# gba-zero.net
KiCad netlist of a schematic drawn in EAGLE
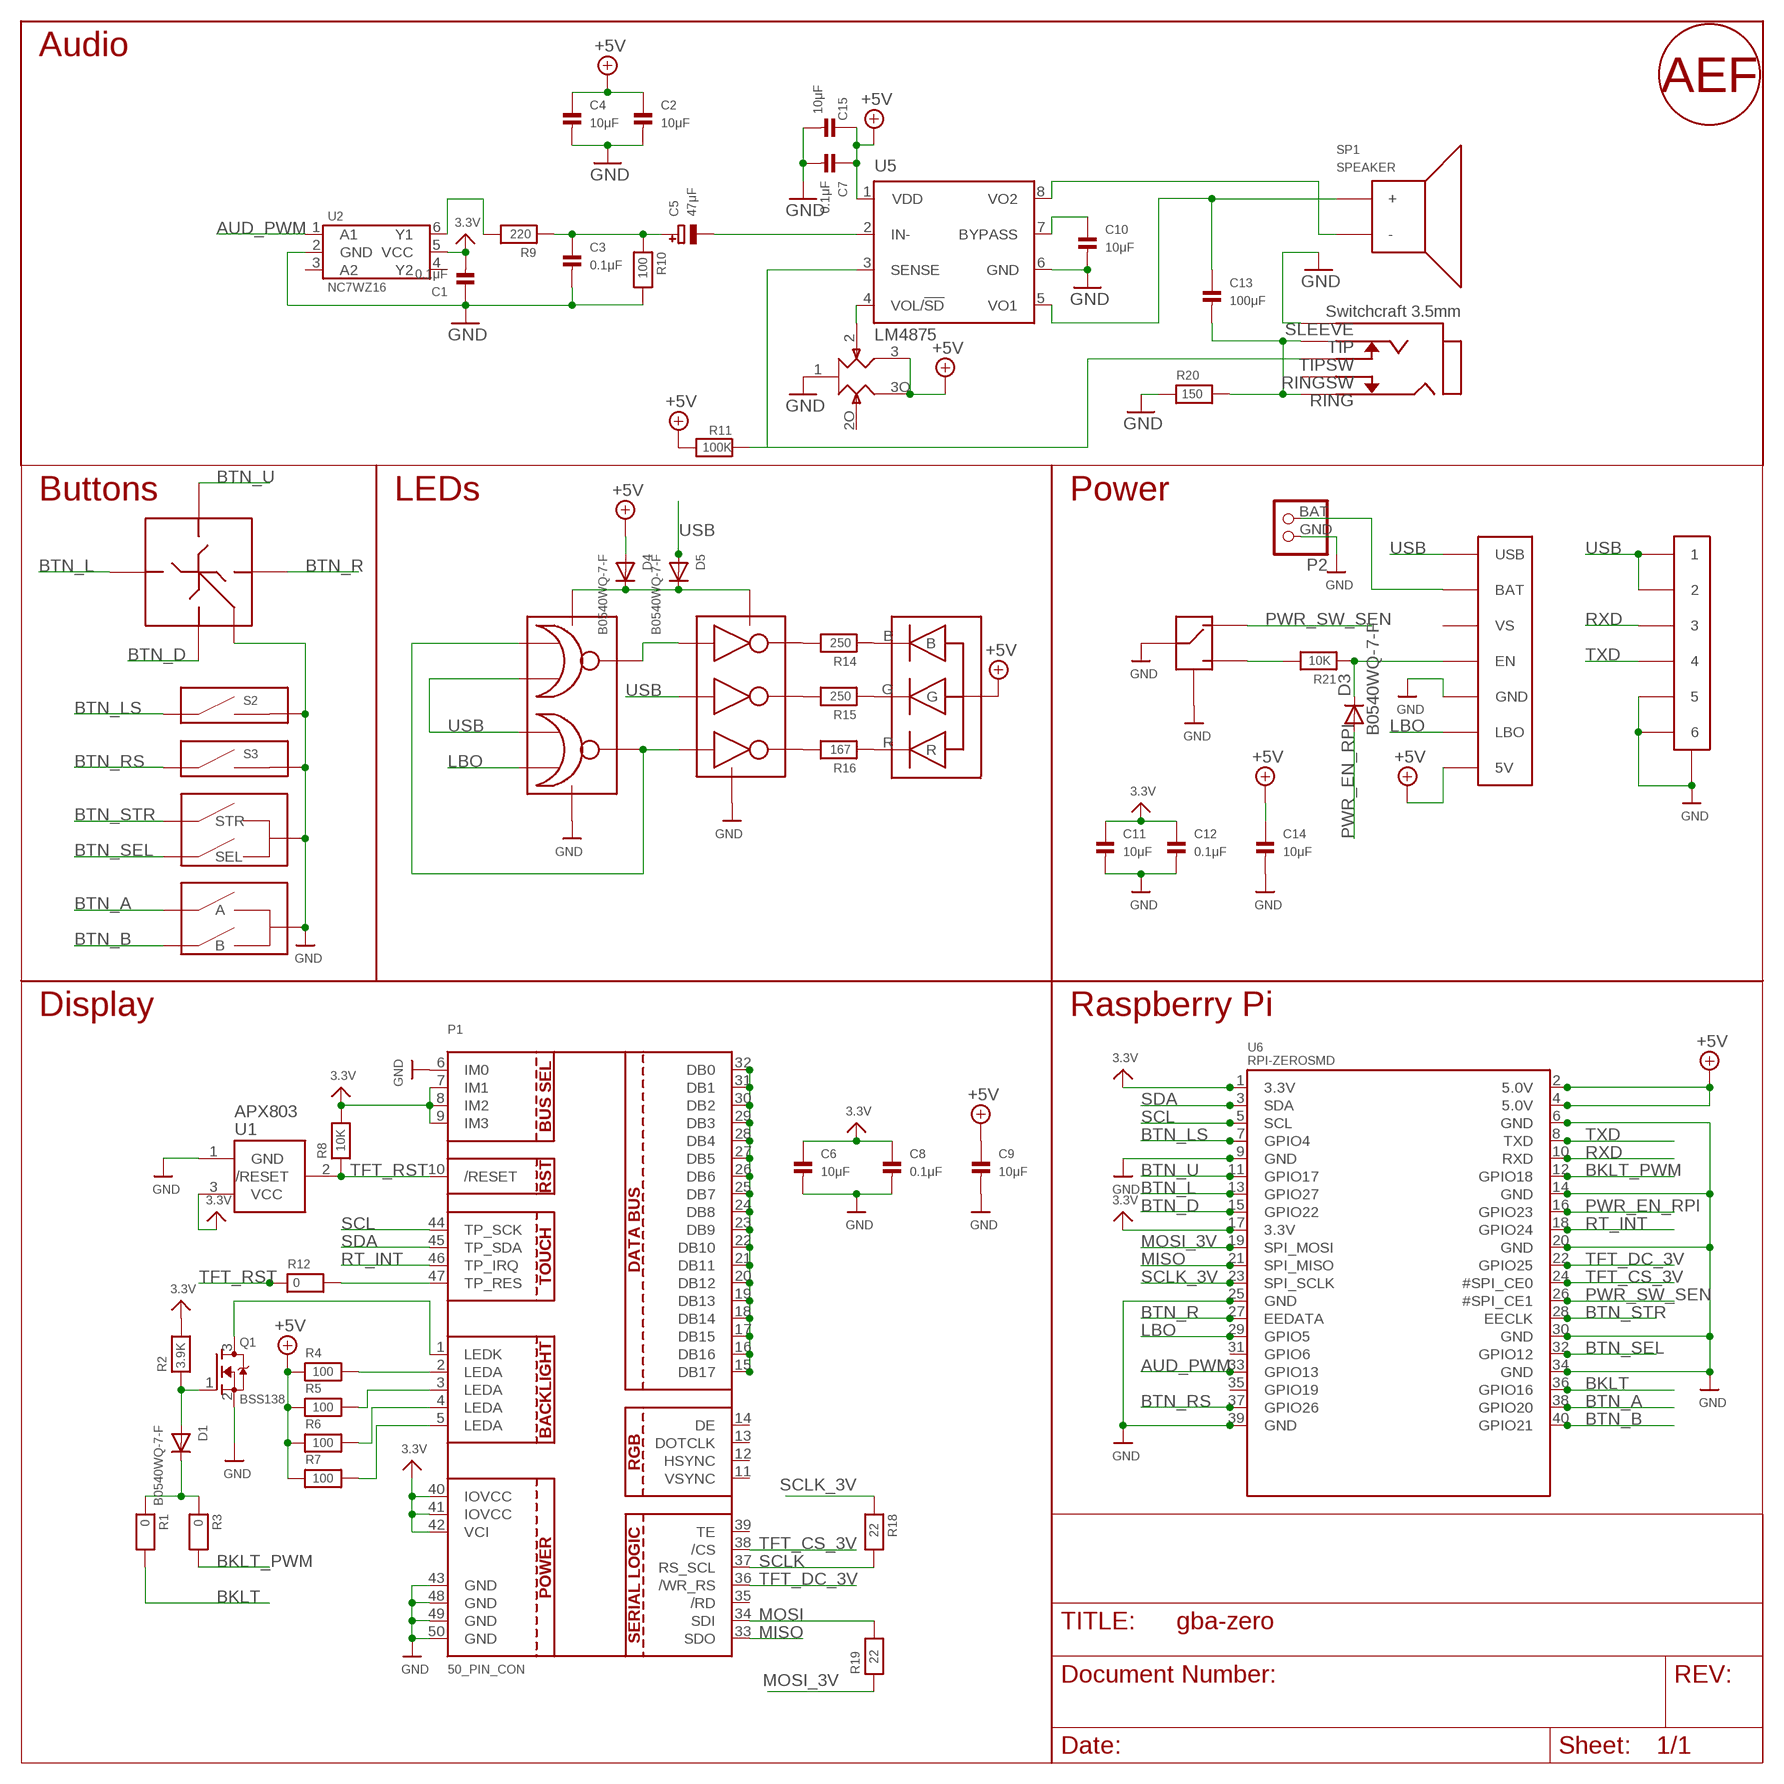
[diagram p0: schematic, sheet 1]

(export (version "E")
  (design (tool "Eeschema 10.0.6"))
  (components
    (comp (ref "C1")
      (value "0.1μF")
      (footprint "eagle-import:0603")
      (libsource (lib "eagle-import") (part "CAP_CERAMIC0603"))
    )
    (comp (ref "C2")
      (value "10μF")
      (footprint "eagle-import:0603")
      (libsource (lib "eagle-import") (part "CAP_CERAMIC0603"))
    )
    (comp (ref "C3")
      (value "0.1μF")
      (footprint "eagle-import:0603")
      (libsource (lib "eagle-import") (part "CAP_CERAMIC0603"))
    )
    (comp (ref "C4")
      (value "10μF")
      (footprint "eagle-import:0603")
      (libsource (lib "eagle-import") (part "CAP_CERAMIC0603"))
    )
    (comp (ref "C5")
      (value "47μF")
      (footprint "eagle-import:EIA6032-28_C-R")
      (libsource (lib "eagle-import") (part "CAP_TANTALUMC/6032_REFLOW"))
    )
    (comp (ref "C6")
      (value "10μF")
      (footprint "eagle-import:0603")
      (libsource (lib "eagle-import") (part "CAP_CERAMIC0603"))
    )
    (comp (ref "C7")
      (value "0.1μF")
      (footprint "eagle-import:0603")
      (libsource (lib "eagle-import") (part "CAP_CERAMIC0603"))
    )
    (comp (ref "C8")
      (value "0.1μF")
      (footprint "eagle-import:0603")
      (libsource (lib "eagle-import") (part "CAP_CERAMIC0603"))
    )
    (comp (ref "C9")
      (value "10μF")
      (footprint "eagle-import:0603")
      (libsource (lib "eagle-import") (part "CAP_CERAMIC0603"))
    )
    (comp (ref "C10")
      (value "10μF")
      (footprint "eagle-import:0603")
      (libsource (lib "eagle-import") (part "CAP_CERAMIC0603"))
    )
    (comp (ref "C11")
      (value "10μF")
      (footprint "eagle-import:0603")
      (libsource (lib "eagle-import") (part "CAP_CERAMIC0603"))
    )
    (comp (ref "C12")
      (value "0.1μF")
      (footprint "eagle-import:0603")
      (libsource (lib "eagle-import") (part "CAP_CERAMIC0603"))
    )
    (comp (ref "C13")
      (value "100μF")
      (footprint "eagle-import:1206")
      (libsource (lib "eagle-import") (part "CAP_CERAMIC1206"))
    )
    (comp (ref "C14")
      (value "10μF")
      (footprint "eagle-import:0603")
      (libsource (lib "eagle-import") (part "CAP_CERAMIC0603"))
    )
    (comp (ref "C15")
      (value "10μF")
      (footprint "eagle-import:0603")
      (libsource (lib "eagle-import") (part "CAP_CERAMIC0603"))
    )
    (comp (ref "D1")
      (value "B0540WQ-7-F")
      (footprint "eagle-import:SOD-123")
      (libsource (lib "eagle-import") (part "DIODESOD-123"))
    )
    (comp (ref "D2")
      (value "LTST-C19HE1WT")
      (footprint "eagle-import:WL-SBCW-0606")
      (libsource (lib "eagle-import") (part "LTST-C19HE1WT"))
    )
    (comp (ref "D3")
      (value "B0540WQ-7-F")
      (footprint "eagle-import:SOD-123")
      (libsource (lib "eagle-import") (part "DIODESOD-123"))
    )
    (comp (ref "D4")
      (value "B0540WQ-7-F")
      (footprint "eagle-import:SOD-123")
      (libsource (lib "eagle-import") (part "DIODESOD-123"))
    )
    (comp (ref "D5")
      (value "B0540WQ-7-F")
      (footprint "eagle-import:SOD-123")
      (libsource (lib "eagle-import") (part "DIODESOD-123"))
    )
    (comp (ref "J1")
      (value "SWTCHCRFT_3.5JACK5-JACK-SMD")
      (footprint "eagle-import:4-JACK-SMD")
      (libsource (lib "eagle-import") (part "SWTCHCRFT_3.5JACK5-JACK-SMD"))
    )
    (comp (ref "P1")
      (value "50_PIN_CON")
      (footprint "eagle-import:FPC-50-CON")
      (libsource (lib "eagle-import") (part "DISP_LCD_CTP28"))
    )
    (comp (ref "P2")
      (value "JST_2PIN")
      (footprint "eagle-import:JSTPH2")
      (libsource (lib "eagle-import") (part "JST_2PIN"))
    )
    (comp (ref "P3")
      (value "LINK_CONNECTOR")
      (footprint "eagle-import:LINK_CONNECTOR")
      (libsource (lib "eagle-import") (part "LINK_CONNECTOR"))
    )
    (comp (ref "Q1")
      (value "BSS138")
      (footprint "eagle-import:SOT23-WIDE")
      (libsource (lib "eagle-import") (part "MOSFET-NWIDE"))
    )
    (comp (ref "R1")
      (value "0")
      (footprint "eagle-import:0603")
      (libsource (lib "eagle-import") (part "RESISTOR0603"))
    )
    (comp (ref "R2")
      (value "3.9K")
      (footprint "eagle-import:0603")
      (libsource (lib "eagle-import") (part "RESISTOR0603"))
    )
    (comp (ref "R3")
      (value "0")
      (footprint "eagle-import:0603")
      (libsource (lib "eagle-import") (part "RESISTOR0603"))
    )
    (comp (ref "R4")
      (value "100")
      (footprint "eagle-import:0603")
      (libsource (lib "eagle-import") (part "RESISTOR0603"))
    )
    (comp (ref "R5")
      (value "100")
      (footprint "eagle-import:0603")
      (libsource (lib "eagle-import") (part "RESISTOR0603"))
    )
    (comp (ref "R6")
      (value "100")
      (footprint "eagle-import:0603")
      (libsource (lib "eagle-import") (part "RESISTOR0603"))
    )
    (comp (ref "R7")
      (value "100")
      (footprint "eagle-import:0603")
      (libsource (lib "eagle-import") (part "RESISTOR0603"))
    )
    (comp (ref "R8")
      (value "10K")
      (footprint "eagle-import:0603")
      (libsource (lib "eagle-import") (part "RESISTOR0603"))
    )
    (comp (ref "R9")
      (value "220")
      (footprint "eagle-import:0603")
      (libsource (lib "eagle-import") (part "RESISTOR0603"))
    )
    (comp (ref "R10")
      (value "100")
      (footprint "eagle-import:0603")
      (libsource (lib "eagle-import") (part "RESISTOR0603"))
    )
    (comp (ref "R11")
      (value "100K")
      (footprint "eagle-import:0603")
      (libsource (lib "eagle-import") (part "RESISTOR0603"))
    )
    (comp (ref "R12")
      (value "0")
      (footprint "eagle-import:0603")
      (libsource (lib "eagle-import") (part "RESISTOR0603"))
    )
    (comp (ref "R14")
      (value "250")
      (footprint "eagle-import:0603")
      (libsource (lib "eagle-import") (part "RESISTOR0603"))
    )
    (comp (ref "R15")
      (value "250")
      (footprint "eagle-import:0603")
      (libsource (lib "eagle-import") (part "RESISTOR0603"))
    )
    (comp (ref "R16")
      (value "167")
      (footprint "eagle-import:0603")
      (libsource (lib "eagle-import") (part "RESISTOR0603"))
    )
    (comp (ref "R17")
      (value "10K")
      (footprint "eagle-import:RK10J12E0A0A")
      (libsource (lib "eagle-import") (part "RK10J12E0A0A"))
    )
    (comp (ref "R18")
      (value "22")
      (footprint "eagle-import:0603")
      (libsource (lib "eagle-import") (part "RESISTOR0603"))
    )
    (comp (ref "R19")
      (value "22")
      (footprint "eagle-import:0603")
      (libsource (lib "eagle-import") (part "RESISTOR0603"))
    )
    (comp (ref "R20")
      (value "150")
      (footprint "eagle-import:0603")
      (libsource (lib "eagle-import") (part "RESISTOR0603"))
    )
    (comp (ref "R21")
      (value "10K")
      (footprint "eagle-import:0603")
      (libsource (lib "eagle-import") (part "RESISTOR0603"))
    )
    (comp (ref "S1")
      (value "D-PAD")
      (footprint "eagle-import:D-PAD")
      (libsource (lib "eagle-import") (part "D-PAD"))
    )
    (comp (ref "S2")
      (value "SHOULDER_BUTTON")
      (footprint "eagle-import:SHOULDER_BUTTON")
      (libsource (lib "eagle-import") (part "SHOULDER_BUTTON"))
    )
    (comp (ref "S3")
      (value "SHOULDER_BUTTON")
      (footprint "eagle-import:SHOULDER_BUTTON")
      (libsource (lib "eagle-import") (part "SHOULDER_BUTTON"))
    )
    (comp (ref "S4")
      (value "START_SELECT_BUTTON")
      (footprint "eagle-import:START_SELECT_BUTTON")
      (libsource (lib "eagle-import") (part "START_SELECT_BUTTON"))
    )
    (comp (ref "S5")
      (value "AB_BUTTON")
      (footprint "eagle-import:AB_BUTTON")
      (libsource (lib "eagle-import") (part "AB_BUTTON"))
    )
    (comp (ref "S6")
      (value "PWR_SWITCH")
      (footprint "eagle-import:PWR-SWITCH")
      (libsource (lib "eagle-import") (part "PWR_SWITCH"))
    )
    (comp (ref "SP1")
      (value "SPEAKER")
      (footprint "eagle-import:SPEAKER")
      (libsource (lib "eagle-import") (part "SPEAKER"))
    )
    (comp (ref "U$1")
      (value "SIGNATURE")
      (footprint "eagle-import:SIGNATURE")
      (libsource (lib "eagle-import") (part "SIGNATURE"))
    )
    (comp (ref "U1")
      (value "APX803")
      (footprint "eagle-import:SOT23")
      (libsource (lib "eagle-import") (part "AXP083-SAG"))
    )
    (comp (ref "U2")
      (value "NC7WZ16")
      (footprint "eagle-import:SC-70-6")
      (libsource (lib "eagle-import") (part "NC7WZ16"))
    )
    (comp (ref "U3")
      (value "74LVC2G02")
      (footprint "eagle-import:TSSOP-8")
      (libsource (lib "eagle-import") (part "74LVC2G02"))
    )
    (comp (ref "U4")
      (value "74LVC3G04")
      (footprint "eagle-import:TSSOP-8")
      (libsource (lib "eagle-import") (part "74LVC3G04"))
    )
    (comp (ref "U5")
      (value "LM4875")
      (footprint "eagle-import:SO-8")
      (libsource (lib "eagle-import") (part "LM4875"))
    )
    (comp (ref "U6")
      (value "RPI-ZEROSMD")
      (footprint "eagle-import:RPI-SMD")
      (libsource (lib "eagle-import") (part "RPI-ZEROSMD"))
    )
    (comp (ref "U7")
      (value "POWERBOOST-1000C")
      (footprint "eagle-import:POWERBOOST-1000C")
      (libsource (lib "eagle-import") (part "POWERBOOST-1000C"))
    )
  )
  (nets
    (net (code "1") (name "+5V") (class "Default")
      (node (ref "C14") (pin "1") (pinfunction "P$1_1") (pintype "passive"))
      (node (ref "C15") (pin "1") (pinfunction "P$1_1") (pintype "passive"))
      (node (ref "C2") (pin "1") (pinfunction "P$1_1") (pintype "passive"))
      (node (ref "C4") (pin "1") (pinfunction "P$1_1") (pintype "passive"))
      (node (ref "C7") (pin "1") (pinfunction "P$1_1") (pintype "passive"))
      (node (ref "C9") (pin "1") (pinfunction "P$1_1") (pintype "passive"))
      (node (ref "D2") (pin "VCC") (pinfunction "VCC_VCC") (pintype "bidirectional"))
      (node (ref "D4") (pin "A") (pinfunction "A_A") (pintype "passive"))
      (node (ref "R11") (pin "2") (pinfunction "2_2") (pintype "passive"))
      (node (ref "R17") (pin "3") (pinfunction "3_3") (pintype "bidirectional"))
      (node (ref "R17") (pin "3O") (pinfunction "3O_3O") (pintype "bidirectional"))
      (node (ref "R4") (pin "1") (pinfunction "1_1") (pintype "passive"))
      (node (ref "R5") (pin "1") (pinfunction "1_1") (pintype "passive"))
      (node (ref "R6") (pin "1") (pinfunction "1_1") (pintype "passive"))
      (node (ref "R7") (pin "1") (pinfunction "1_1") (pintype "passive"))
      (node (ref "U5") (pin "1") (pinfunction "VDD_1") (pintype "power_in"))
      (node (ref "U6") (pin "2") (pinfunction "5.0V_2") (pintype "bidirectional"))
      (node (ref "U6") (pin "4") (pinfunction "5.0V_4") (pintype "bidirectional"))
      (node (ref "U7") (pin "5V") (pinfunction "5V_5V") (pintype "bidirectional"))
    )
    (net (code "2") (name "/AUD_PWM") (class "Default")
      (node (ref "U2") (pin "1") (pinfunction "A1_1") (pintype "bidirectional"))
      (node (ref "U6") (pin "33") (pinfunction "GPIO13_33") (pintype "bidirectional"))
    )
    (net (code "3") (name "/BKLT") (class "Default")
      (node (ref "R1") (pin "2") (pinfunction "2_2") (pintype "passive"))
      (node (ref "U6") (pin "36") (pinfunction "GPIO16_36") (pintype "bidirectional"))
    )
    (net (code "4") (name "/BKLT_PWM") (class "Default")
      (node (ref "R3") (pin "2") (pinfunction "2_2") (pintype "passive"))
      (node (ref "U6") (pin "12") (pinfunction "GPIO18_12") (pintype "bidirectional"))
    )
    (net (code "5") (name "/BTN_A") (class "Default")
      (node (ref "S5") (pin "A@1") (pinfunction "A_A@1") (pintype "bidirectional"))
      (node (ref "S5") (pin "A@2") (pinfunction "A_A@2") (pintype "bidirectional"))
      (node (ref "U6") (pin "38") (pinfunction "GPIO20_38") (pintype "bidirectional"))
    )
    (net (code "6") (name "/BTN_B") (class "Default")
      (node (ref "S5") (pin "B@1") (pinfunction "B_B@1") (pintype "bidirectional"))
      (node (ref "S5") (pin "B@2") (pinfunction "B_B@2") (pintype "bidirectional"))
      (node (ref "U6") (pin "40") (pinfunction "GPIO21_40") (pintype "bidirectional"))
    )
    (net (code "7") (name "/BTN_D") (class "Default")
      (node (ref "S1") (pin "DOWN") (pinfunction "DOWN_DOWN") (pintype "bidirectional"))
      (node (ref "U6") (pin "15") (pinfunction "GPIO22_15") (pintype "bidirectional"))
    )
    (net (code "8") (name "/BTN_L") (class "Default")
      (node (ref "S1") (pin "LEFT") (pinfunction "LEFT_LEFT") (pintype "bidirectional"))
      (node (ref "U6") (pin "13") (pinfunction "GPIO27_13") (pintype "bidirectional"))
    )
    (net (code "9") (name "/BTN_LS") (class "Default")
      (node (ref "S2") (pin "SW") (pinfunction "1_SW") (pintype "bidirectional"))
      (node (ref "U6") (pin "7") (pinfunction "GPIO4_7") (pintype "bidirectional"))
    )
    (net (code "10") (name "/BTN_R") (class "Default")
      (node (ref "S1") (pin "RIGHT") (pinfunction "RIGHT_RIGHT") (pintype "bidirectional"))
      (node (ref "U6") (pin "27") (pinfunction "EEDATA_27") (pintype "bidirectional"))
    )
    (net (code "11") (name "/BTN_RS") (class "Default")
      (node (ref "S3") (pin "SW") (pinfunction "1_SW") (pintype "bidirectional"))
      (node (ref "U6") (pin "37") (pinfunction "GPIO26_37") (pintype "bidirectional"))
    )
    (net (code "12") (name "/BTN_SEL") (class "Default")
      (node (ref "S4") (pin "SEL") (pinfunction "SEL_SEL") (pintype "bidirectional"))
      (node (ref "U6") (pin "32") (pinfunction "GPIO12_32") (pintype "bidirectional"))
    )
    (net (code "13") (name "/BTN_STR") (class "Default")
      (node (ref "S4") (pin "STR") (pinfunction "STR_STR") (pintype "bidirectional"))
      (node (ref "U6") (pin "28") (pinfunction "EECLK_28") (pintype "bidirectional"))
    )
    (net (code "14") (name "/BTN_U") (class "Default")
      (node (ref "S1") (pin "UP") (pinfunction "UP_UP") (pintype "bidirectional"))
      (node (ref "U6") (pin "11") (pinfunction "GPIO17_11") (pintype "bidirectional"))
    )
    (net (code "15") (name "/LBO") (class "Default")
      (node (ref "U3") (pin "6") (pinfunction "2B_6") (pintype "bidirectional"))
      (node (ref "U6") (pin "29") (pinfunction "GPIO5_29") (pintype "bidirectional"))
      (node (ref "U7") (pin "LBO") (pinfunction "LBO_LBO") (pintype "bidirectional"))
    )
    (net (code "16") (name "/MISO") (class "Default")
      (node (ref "P1") (pin "33") (pinfunction "SDO_33") (pintype "bidirectional"))
      (node (ref "U6") (pin "21") (pinfunction "SPI_MISO_21") (pintype "bidirectional"))
    )
    (net (code "17") (name "/MOSI") (class "Default")
      (node (ref "P1") (pin "34") (pinfunction "SDI_34") (pintype "bidirectional"))
      (node (ref "R19") (pin "2") (pinfunction "2_2") (pintype "passive"))
    )
    (net (code "18") (name "/MOSI_3V") (class "Default")
      (node (ref "R19") (pin "1") (pinfunction "1_1") (pintype "passive"))
      (node (ref "U6") (pin "19") (pinfunction "SPI_MOSI_19") (pintype "bidirectional"))
    )
    (net (code "19") (name "/PWR_EN_RPI") (class "Default")
      (node (ref "D3") (pin "A") (pinfunction "A_A") (pintype "passive"))
      (node (ref "U6") (pin "16") (pinfunction "GPIO23_16") (pintype "bidirectional"))
    )
    (net (code "20") (name "/PWR_SW_SEN") (class "Default")
      (node (ref "S6") (pin "L") (pinfunction "L_L") (pintype "bidirectional"))
      (node (ref "U6") (pin "26") (pinfunction "#SPI_CE1_26") (pintype "bidirectional"))
    )
    (net (code "21") (name "/RT_INT") (class "Default")
      (node (ref "P1") (pin "46") (pinfunction "TP_IRQ_46") (pintype "bidirectional"))
      (node (ref "U6") (pin "18") (pinfunction "GPIO24_18") (pintype "bidirectional"))
    )
    (net (code "22") (name "/RXD") (class "Default")
      (node (ref "P3") (pin "3") (pinfunction "3_3") (pintype "bidirectional"))
      (node (ref "U6") (pin "10") (pinfunction "RXD_10") (pintype "bidirectional"))
    )
    (net (code "23") (name "/SCL") (class "Default")
      (node (ref "P1") (pin "44") (pinfunction "TP_SCK_44") (pintype "bidirectional"))
      (node (ref "U6") (pin "5") (pinfunction "SCL_5") (pintype "bidirectional"))
    )
    (net (code "24") (name "/SCLK") (class "Default")
      (node (ref "P1") (pin "37") (pinfunction "RS_SCL_37") (pintype "bidirectional"))
      (node (ref "R18") (pin "2") (pinfunction "2_2") (pintype "passive"))
    )
    (net (code "25") (name "/SCLK_3V") (class "Default")
      (node (ref "R18") (pin "1") (pinfunction "1_1") (pintype "passive"))
      (node (ref "U6") (pin "23") (pinfunction "SPI_SCLK_23") (pintype "bidirectional"))
    )
    (net (code "26") (name "/SDA") (class "Default")
      (node (ref "P1") (pin "45") (pinfunction "TP_SDA_45") (pintype "bidirectional"))
      (node (ref "U6") (pin "3") (pinfunction "SDA_3") (pintype "bidirectional"))
    )
    (net (code "27") (name "/TFT_CS_3V") (class "Default")
      (node (ref "P1") (pin "38") (pinfunction "/CS_38") (pintype "bidirectional"))
      (node (ref "U6") (pin "24") (pinfunction "#SPI_CE0_24") (pintype "bidirectional"))
    )
    (net (code "28") (name "/TFT_DC_3V") (class "Default")
      (node (ref "P1") (pin "36") (pinfunction "/WR_RS_36") (pintype "bidirectional"))
      (node (ref "U6") (pin "22") (pinfunction "GPIO25_22") (pintype "bidirectional"))
    )
    (net (code "29") (name "/TFT_RST") (class "Default")
      (node (ref "P1") (pin "10") (pinfunction "/RESET_10") (pintype "bidirectional"))
      (node (ref "R12") (pin "1") (pinfunction "1_1") (pintype "passive"))
      (node (ref "R8") (pin "1") (pinfunction "1_1") (pintype "passive"))
      (node (ref "U1") (pin "2") (pinfunction "/RESET_2") (pintype "output"))
    )
    (net (code "30") (name "/TXD") (class "Default")
      (node (ref "P3") (pin "4") (pinfunction "4_4") (pintype "bidirectional"))
      (node (ref "U6") (pin "8") (pinfunction "TXD_8") (pintype "bidirectional"))
    )
    (net (code "31") (name "/USB") (class "Default")
      (node (ref "D5") (pin "A") (pinfunction "A_A") (pintype "passive"))
      (node (ref "P3") (pin "1") (pinfunction "1_1") (pintype "bidirectional"))
      (node (ref "P3") (pin "2") (pinfunction "2_2") (pintype "bidirectional"))
      (node (ref "U3") (pin "2") (pinfunction "1B_2") (pintype "bidirectional"))
      (node (ref "U3") (pin "5") (pinfunction "2A_5") (pintype "bidirectional"))
      (node (ref "U4") (pin "3") (pinfunction "2A_3") (pintype "bidirectional"))
      (node (ref "U7") (pin "USB") (pinfunction "USB_USB") (pintype "bidirectional"))
    )
    (net (code "32") (name "3.3V") (class "Default")
      (node (ref "C1") (pin "2") (pinfunction "P$2_2") (pintype "passive"))
      (node (ref "C11") (pin "1") (pinfunction "P$1_1") (pintype "passive"))
      (node (ref "C12") (pin "1") (pinfunction "P$1_1") (pintype "passive"))
      (node (ref "C6") (pin "1") (pinfunction "P$1_1") (pintype "passive"))
      (node (ref "C8") (pin "1") (pinfunction "P$1_1") (pintype "passive"))
      (node (ref "P1") (pin "40") (pinfunction "IOVCC_40") (pintype "bidirectional"))
      (node (ref "P1") (pin "41") (pinfunction "IOVCC_41") (pintype "bidirectional"))
      (node (ref "P1") (pin "42") (pinfunction "VCI_42") (pintype "bidirectional"))
      (node (ref "P1") (pin "7") (pinfunction "IM1_7") (pintype "bidirectional"))
      (node (ref "P1") (pin "8") (pinfunction "IM2_8") (pintype "bidirectional"))
      (node (ref "P1") (pin "9") (pinfunction "IM3_9") (pintype "bidirectional"))
      (node (ref "R2") (pin "2") (pinfunction "2_2") (pintype "passive"))
      (node (ref "R8") (pin "2") (pinfunction "2_2") (pintype "passive"))
      (node (ref "U1") (pin "3") (pinfunction "VCC_3") (pintype "power_in"))
      (node (ref "U2") (pin "5") (pinfunction "VCC_5") (pintype "bidirectional"))
      (node (ref "U6") (pin "1") (pinfunction "3.3V_1") (pintype "bidirectional"))
      (node (ref "U6") (pin "17") (pinfunction "3.3V_17") (pintype "bidirectional"))
    )
    (net (code "33") (name "GND") (class "Default")
      (node (ref "C1") (pin "1") (pinfunction "P$1_1") (pintype "passive"))
      (node (ref "C10") (pin "2") (pinfunction "P$2_2") (pintype "passive"))
      (node (ref "C11") (pin "2") (pinfunction "P$2_2") (pintype "passive"))
      (node (ref "C12") (pin "2") (pinfunction "P$2_2") (pintype "passive"))
      (node (ref "C14") (pin "2") (pinfunction "P$2_2") (pintype "passive"))
      (node (ref "C15") (pin "2") (pinfunction "P$2_2") (pintype "passive"))
      (node (ref "C2") (pin "2") (pinfunction "P$2_2") (pintype "passive"))
      (node (ref "C3") (pin "2") (pinfunction "P$2_2") (pintype "passive"))
      (node (ref "C4") (pin "2") (pinfunction "P$2_2") (pintype "passive"))
      (node (ref "C6") (pin "2") (pinfunction "P$2_2") (pintype "passive"))
      (node (ref "C7") (pin "2") (pinfunction "P$2_2") (pintype "passive"))
      (node (ref "C8") (pin "2") (pinfunction "P$2_2") (pintype "passive"))
      (node (ref "C9") (pin "2") (pinfunction "P$2_2") (pintype "passive"))
      (node (ref "J1") (pin "1") (pinfunction "1_1") (pintype "bidirectional"))
      (node (ref "P1") (pin "43") (pinfunction "GND_43") (pintype "bidirectional"))
      (node (ref "P1") (pin "48") (pinfunction "GND_48") (pintype "bidirectional"))
      (node (ref "P1") (pin "49") (pinfunction "GND_49") (pintype "bidirectional"))
      (node (ref "P1") (pin "50") (pinfunction "GND_50") (pintype "bidirectional"))
      (node (ref "P1") (pin "6") (pinfunction "IM0_6") (pintype "bidirectional"))
      (node (ref "P2") (pin "GND") (pinfunction "1_GND") (pintype "passive"))
      (node (ref "P3") (pin "5") (pinfunction "5_5") (pintype "bidirectional"))
      (node (ref "P3") (pin "6") (pinfunction "6_6") (pintype "bidirectional"))
      (node (ref "P3") (pin "GND@1") (pinfunction "GND_GND@1") (pintype "bidirectional"))
      (node (ref "P3") (pin "GND@2") (pinfunction "GND_GND@2") (pintype "bidirectional"))
      (node (ref "Q1") (pin "2") (pinfunction "S_2") (pintype "bidirectional"))
      (node (ref "R10") (pin "2") (pinfunction "2_2") (pintype "passive"))
      (node (ref "R17") (pin "1") (pinfunction "1_1") (pintype "bidirectional"))
      (node (ref "R20") (pin "1") (pinfunction "1_1") (pintype "passive"))
      (node (ref "S1") (pin "GND@1") (pinfunction "GND_GND@1") (pintype "bidirectional"))
      (node (ref "S1") (pin "GND@2") (pinfunction "GND_GND@2") (pintype "bidirectional"))
      (node (ref "S1") (pin "GND@3") (pinfunction "GND_GND@3") (pintype "bidirectional"))
      (node (ref "S1") (pin "GND@4") (pinfunction "GND_GND@4") (pintype "bidirectional"))
      (node (ref "S2") (pin "GND@1") (pinfunction "2_GND@1") (pintype "bidirectional"))
      (node (ref "S2") (pin "GND@2") (pinfunction "2_GND@2") (pintype "bidirectional"))
      (node (ref "S2") (pin "GND@3") (pinfunction "2_GND@3") (pintype "bidirectional"))
      (node (ref "S3") (pin "GND@1") (pinfunction "2_GND@1") (pintype "bidirectional"))
      (node (ref "S3") (pin "GND@2") (pinfunction "2_GND@2") (pintype "bidirectional"))
      (node (ref "S3") (pin "GND@3") (pinfunction "2_GND@3") (pintype "bidirectional"))
      (node (ref "S4") (pin "GND@1") (pinfunction "GND_GND@1") (pintype "bidirectional"))
      (node (ref "S4") (pin "GND@2") (pinfunction "GND_GND@2") (pintype "bidirectional"))
      (node (ref "S4") (pin "GND@3") (pinfunction "GND_GND@3") (pintype "bidirectional"))
      (node (ref "S4") (pin "GND@4") (pinfunction "GND_GND@4") (pintype "bidirectional"))
      (node (ref "S5") (pin "GND@1") (pinfunction "GND_GND@1") (pintype "bidirectional"))
      (node (ref "S5") (pin "GND@2") (pinfunction "GND_GND@2") (pintype "bidirectional"))
      (node (ref "S5") (pin "GND@3") (pinfunction "GND_GND@3") (pintype "bidirectional"))
      (node (ref "S5") (pin "GND@4") (pinfunction "GND_GND@4") (pintype "bidirectional"))
      (node (ref "S6") (pin "C@1") (pinfunction "C_C@1") (pintype "bidirectional"))
      (node (ref "S6") (pin "C@2") (pinfunction "C_C@2") (pintype "bidirectional"))
      (node (ref "S6") (pin "GND@1") (pinfunction "GND_GND@1") (pintype "bidirectional"))
      (node (ref "S6") (pin "GND@2") (pinfunction "GND_GND@2") (pintype "bidirectional"))
      (node (ref "U1") (pin "1") (pinfunction "GND_1") (pintype "power_in"))
      (node (ref "U2") (pin "2") (pinfunction "GND_2") (pintype "bidirectional"))
      (node (ref "U3") (pin "4") (pinfunction "GND_4") (pintype "bidirectional"))
      (node (ref "U4") (pin "4") (pinfunction "GND_4") (pintype "bidirectional"))
      (node (ref "U5") (pin "6") (pinfunction "GND_6") (pintype "power_in"))
      (node (ref "U6") (pin "14") (pinfunction "GND_14") (pintype "power_in"))
      (node (ref "U6") (pin "20") (pinfunction "GND_20") (pintype "power_in"))
      (node (ref "U6") (pin "25") (pinfunction "GND_25") (pintype "power_in"))
      (node (ref "U6") (pin "30") (pinfunction "GND_30") (pintype "power_in"))
      (node (ref "U6") (pin "34") (pinfunction "GND_34") (pintype "power_in"))
      (node (ref "U6") (pin "39") (pinfunction "GND_39") (pintype "power_in"))
      (node (ref "U6") (pin "6") (pinfunction "GND_6") (pintype "power_in"))
      (node (ref "U6") (pin "9") (pinfunction "GND_9") (pintype "power_in"))
      (node (ref "U7") (pin "GND@1") (pinfunction "GND_GND@1") (pintype "bidirectional"))
      (node (ref "U7") (pin "GND@2") (pinfunction "GND_GND@2") (pintype "bidirectional"))
    )
    (net (code "34") (name "Net-(C3-P$1)") (class "Default")
      (node (ref "C3") (pin "1") (pinfunction "P$1_1") (pintype "passive"))
      (node (ref "C5") (pin "+") (pinfunction "+_+") (pintype "passive"))
      (node (ref "R10") (pin "1") (pinfunction "1_1") (pintype "passive"))
      (node (ref "R9") (pin "1") (pinfunction "1_1") (pintype "passive"))
    )
    (net (code "35") (name "Net-(C10-P$1)") (class "Default")
      (node (ref "C10") (pin "1") (pinfunction "P$1_1") (pintype "passive"))
      (node (ref "U5") (pin "7") (pinfunction "BYPASS_7") (pintype "passive"))
    )
    (net (code "36") (name "Net-(C13-P$1)") (class "Default")
      (node (ref "C13") (pin "1") (pinfunction "P$1_1") (pintype "passive"))
      (node (ref "SP1") (pin "1") (pinfunction "+_1") (pintype "bidirectional"))
      (node (ref "U5") (pin "5") (pinfunction "VO1_5") (pintype "output"))
    )
    (net (code "37") (name "Net-(C13-P$2)") (class "Default")
      (node (ref "C13") (pin "2") (pinfunction "P$2_2") (pintype "passive"))
      (node (ref "J1") (pin "2") (pinfunction "2_2") (pintype "bidirectional"))
      (node (ref "J1") (pin "3") (pinfunction "3_3") (pintype "bidirectional"))
      (node (ref "R20") (pin "2") (pinfunction "2_2") (pintype "passive"))
    )
    (net (code "38") (name "Net-(D1-PadC)") (class "Default")
      (node (ref "D1") (pin "C") (pinfunction "C_C") (pintype "passive"))
      (node (ref "R1") (pin "1") (pinfunction "1_1") (pintype "passive"))
      (node (ref "R3") (pin "1") (pinfunction "1_1") (pintype "passive"))
    )
    (net (code "39") (name "Net-(D2-PadB)") (class "Default")
      (node (ref "D2") (pin "B") (pinfunction "B_B") (pintype "bidirectional"))
      (node (ref "R14") (pin "1") (pinfunction "1_1") (pintype "passive"))
    )
    (net (code "40") (name "Net-(D2-PadG)") (class "Default")
      (node (ref "D2") (pin "G") (pinfunction "G_G") (pintype "bidirectional"))
      (node (ref "R15") (pin "1") (pinfunction "1_1") (pintype "passive"))
    )
    (net (code "41") (name "Net-(D2-PadR)") (class "Default")
      (node (ref "D2") (pin "R") (pinfunction "R_R") (pintype "bidirectional"))
      (node (ref "R16") (pin "1") (pinfunction "1_1") (pintype "passive"))
    )
    (net (code "42") (name "Net-(D3-PadC)") (class "Default")
      (node (ref "D3") (pin "C") (pinfunction "C_C") (pintype "passive"))
      (node (ref "R21") (pin "1") (pinfunction "1_1") (pintype "passive"))
      (node (ref "U7") (pin "EN") (pinfunction "EN_EN") (pintype "bidirectional"))
    )
    (net (code "43") (name "Net-(P1-DB0)") (class "Default")
      (node (ref "P1") (pin "15") (pinfunction "DB17_15") (pintype "bidirectional"))
      (node (ref "P1") (pin "16") (pinfunction "DB16_16") (pintype "bidirectional"))
      (node (ref "P1") (pin "17") (pinfunction "DB15_17") (pintype "bidirectional"))
      (node (ref "P1") (pin "18") (pinfunction "DB14_18") (pintype "bidirectional"))
      (node (ref "P1") (pin "19") (pinfunction "DB13_19") (pintype "bidirectional"))
      (node (ref "P1") (pin "20") (pinfunction "DB12_20") (pintype "bidirectional"))
      (node (ref "P1") (pin "21") (pinfunction "DB11_21") (pintype "bidirectional"))
      (node (ref "P1") (pin "22") (pinfunction "DB10_22") (pintype "bidirectional"))
      (node (ref "P1") (pin "23") (pinfunction "DB9_23") (pintype "bidirectional"))
      (node (ref "P1") (pin "24") (pinfunction "DB8_24") (pintype "bidirectional"))
      (node (ref "P1") (pin "25") (pinfunction "DB7_25") (pintype "bidirectional"))
      (node (ref "P1") (pin "26") (pinfunction "DB6_26") (pintype "bidirectional"))
      (node (ref "P1") (pin "27") (pinfunction "DB5_27") (pintype "bidirectional"))
      (node (ref "P1") (pin "28") (pinfunction "DB4_28") (pintype "bidirectional"))
      (node (ref "P1") (pin "29") (pinfunction "DB3_29") (pintype "bidirectional"))
      (node (ref "P1") (pin "30") (pinfunction "DB2_30") (pintype "bidirectional"))
      (node (ref "P1") (pin "31") (pinfunction "DB1_31") (pintype "bidirectional"))
      (node (ref "P1") (pin "32") (pinfunction "DB0_32") (pintype "bidirectional"))
    )
    (net (code "44") (name "Net-(P1-LEDA-Pad2)") (class "Default")
      (node (ref "P1") (pin "2") (pinfunction "LEDA_2") (pintype "bidirectional"))
      (node (ref "R4") (pin "2") (pinfunction "2_2") (pintype "passive"))
    )
    (net (code "45") (name "Net-(P1-LEDA-Pad3)") (class "Default")
      (node (ref "P1") (pin "3") (pinfunction "LEDA_3") (pintype "bidirectional"))
      (node (ref "R5") (pin "2") (pinfunction "2_2") (pintype "passive"))
    )
    (net (code "46") (name "Net-(P1-LEDA-Pad4)") (class "Default")
      (node (ref "P1") (pin "4") (pinfunction "LEDA_4") (pintype "bidirectional"))
      (node (ref "R6") (pin "2") (pinfunction "2_2") (pintype "passive"))
    )
    (net (code "47") (name "Net-(P1-LEDA-Pad5)") (class "Default")
      (node (ref "P1") (pin "5") (pinfunction "LEDA_5") (pintype "bidirectional"))
      (node (ref "R7") (pin "2") (pinfunction "2_2") (pintype "passive"))
    )
    (net (code "48") (name "Net-(P1-LEDK)") (class "Default")
      (node (ref "P1") (pin "1") (pinfunction "LEDK_1") (pintype "bidirectional"))
      (node (ref "Q1") (pin "3") (pinfunction "D_3") (pintype "bidirectional"))
    )
    (net (code "49") (name "Net-(P1-TP_RES)") (class "Default")
      (node (ref "P1") (pin "47") (pinfunction "TP_RES_47") (pintype "bidirectional"))
      (node (ref "R12") (pin "2") (pinfunction "2_2") (pintype "passive"))
    )
    (net (code "50") (name "Net-(P2-2)") (class "Default")
      (node (ref "P2") (pin "BAT") (pinfunction "2_BAT") (pintype "passive"))
      (node (ref "U7") (pin "BAT") (pinfunction "BAT_BAT") (pintype "bidirectional"))
    )
    (net (code "51") (name "Net-(Q1-G)") (class "Default")
      (node (ref "D1") (pin "A") (pinfunction "A_A") (pintype "passive"))
      (node (ref "Q1") (pin "1") (pinfunction "G_1") (pintype "bidirectional"))
      (node (ref "R2") (pin "1") (pinfunction "1_1") (pintype "passive"))
    )
    (net (code "52") (name "Net-(R21-Pad2)") (class "Default")
      (node (ref "R21") (pin "2") (pinfunction "2_2") (pintype "passive"))
      (node (ref "S6") (pin "R") (pinfunction "R_R") (pintype "bidirectional"))
    )
    (net (code "53") (name "Net-(SP1--)") (class "Default")
      (node (ref "SP1") (pin "2") (pinfunction "-_2") (pintype "bidirectional"))
      (node (ref "U5") (pin "8") (pinfunction "VO2_8") (pintype "output"))
    )
    (net (code "54") (name "Net-(U2-Y1)") (class "Default")
      (node (ref "R9") (pin "2") (pinfunction "2_2") (pintype "passive"))
      (node (ref "U2") (pin "6") (pinfunction "Y1_6") (pintype "bidirectional"))
    )
    (net (code "55") (name "Net-(U3-1A)") (class "Default")
      (node (ref "U3") (pin "1") (pinfunction "1A_1") (pintype "bidirectional"))
      (node (ref "U3") (pin "3") (pinfunction "2Y_3") (pintype "bidirectional"))
      (node (ref "U4") (pin "6") (pinfunction "3A_6") (pintype "bidirectional"))
    )
    (net (code "56") (name "Net-(U3-1Y)") (class "Default")
      (node (ref "U3") (pin "7") (pinfunction "1Y_7") (pintype "bidirectional"))
      (node (ref "U4") (pin "1") (pinfunction "1A_1") (pintype "bidirectional"))
    )
    (net (code "57") (name "Net-(U3-VCC)") (class "Default")
      (node (ref "D4") (pin "C") (pinfunction "C_C") (pintype "passive"))
      (node (ref "D5") (pin "C") (pinfunction "C_C") (pintype "passive"))
      (node (ref "U3") (pin "8") (pinfunction "VCC_8") (pintype "bidirectional"))
      (node (ref "U4") (pin "8") (pinfunction "VCC_8") (pintype "bidirectional"))
    )
    (net (code "58") (name "Net-(U4-1Y)") (class "Default")
      (node (ref "R14") (pin "2") (pinfunction "2_2") (pintype "passive"))
      (node (ref "U4") (pin "7") (pinfunction "1Y_7") (pintype "bidirectional"))
    )
    (net (code "59") (name "Net-(U4-2Y)") (class "Default")
      (node (ref "R15") (pin "2") (pinfunction "2_2") (pintype "passive"))
      (node (ref "U4") (pin "5") (pinfunction "2Y_5") (pintype "bidirectional"))
    )
    (net (code "60") (name "Net-(U4-3Y)") (class "Default")
      (node (ref "R16") (pin "2") (pinfunction "2_2") (pintype "passive"))
      (node (ref "U4") (pin "2") (pinfunction "3Y_2") (pintype "bidirectional"))
    )
    (net (code "61") (name "Net-(U5-IN-)") (class "Default")
      (node (ref "C5") (pin "-") (pinfunction "-_-") (pintype "passive"))
      (node (ref "U5") (pin "2") (pinfunction "IN-_2") (pintype "input"))
    )
    (net (code "62") (name "Net-(U5-SENSE)") (class "Default")
      (node (ref "J1") (pin "5") (pinfunction "5_5") (pintype "bidirectional"))
      (node (ref "R11") (pin "1") (pinfunction "1_1") (pintype "passive"))
      (node (ref "U5") (pin "3") (pinfunction "SENSE_3") (pintype "input"))
    )
    (net (code "63") (name "Net-(U5-VOL{slash}~{SD})") (class "Default")
      (node (ref "R17") (pin "2") (pinfunction "2_2") (pintype "bidirectional"))
      (node (ref "U5") (pin "4") (pinfunction "VOL/~{SD}_4") (pintype "input"))
    )
    (net (code "64") (name "unconnected-(J1-Pad4)") (class "Default")
      (node (ref "J1") (pin "4") (pinfunction "4_4") (pintype "bidirectional"))
    )
    (net (code "65") (name "unconnected-(P1-DE-Pad14)") (class "Default")
      (node (ref "P1") (pin "14") (pinfunction "DE_14") (pintype "bidirectional"))
    )
    (net (code "66") (name "unconnected-(P1-DOTCLK-Pad13)") (class "Default")
      (node (ref "P1") (pin "13") (pinfunction "DOTCLK_13") (pintype "bidirectional"))
    )
    (net (code "67") (name "unconnected-(P1-HSYNC-Pad12)") (class "Default")
      (node (ref "P1") (pin "12") (pinfunction "HSYNC_12") (pintype "bidirectional"))
    )
    (net (code "68") (name "unconnected-(P1-TE-Pad39)") (class "Default")
      (node (ref "P1") (pin "39") (pinfunction "TE_39") (pintype "bidirectional"))
    )
    (net (code "69") (name "unconnected-(P1-VSYNC-Pad11)") (class "Default")
      (node (ref "P1") (pin "11") (pinfunction "VSYNC_11") (pintype "bidirectional"))
    )
    (net (code "70") (name "unconnected-(P1-{slash}RD-Pad35)") (class "Default")
      (node (ref "P1") (pin "35") (pinfunction "/RD_35") (pintype "bidirectional"))
    )
    (net (code "71") (name "unconnected-(R17-Pad2O)") (class "Default")
      (node (ref "R17") (pin "2O") (pinfunction "2O_2O") (pintype "bidirectional"))
    )
    (net (code "72") (name "unconnected-(U2-A2-Pad3)") (class "Default")
      (node (ref "U2") (pin "3") (pinfunction "A2_3") (pintype "bidirectional"))
    )
    (net (code "73") (name "unconnected-(U2-Y2-Pad4)") (class "Default")
      (node (ref "U2") (pin "4") (pinfunction "Y2_4") (pintype "bidirectional"))
    )
    (net (code "74") (name "unconnected-(U6-GPIO6-Pad31)") (class "Default")
      (node (ref "U6") (pin "31") (pinfunction "GPIO6_31") (pintype "bidirectional"))
    )
    (net (code "75") (name "unconnected-(U6-GPIO19-Pad35)") (class "Default")
      (node (ref "U6") (pin "35") (pinfunction "GPIO19_35") (pintype "bidirectional"))
    )
    (net (code "76") (name "unconnected-(U7-PadVS)") (class "Default")
      (node (ref "U7") (pin "VS") (pinfunction "VS_VS") (pintype "bidirectional"))
    )
  )
)
